# LCDmain.net
KiCad netlist of a schematic drawn in EAGLE
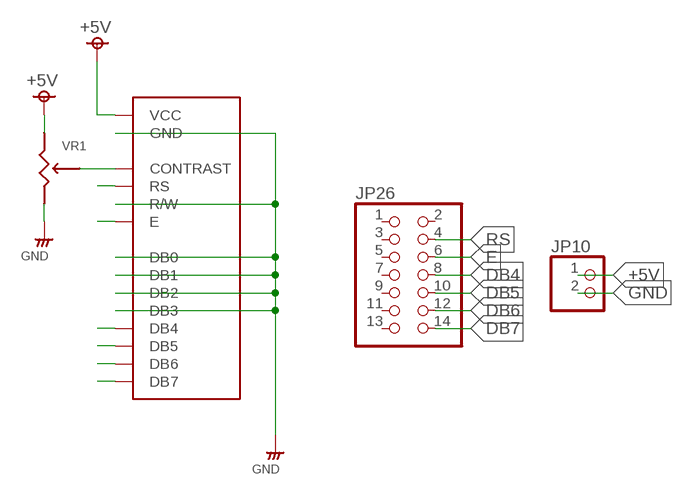
[diagram p0: schematic, sheet 1]

(export (version "E")
  (design (tool "Eeschema 10.0.6"))
  (components
    (comp (ref "JP10")
      (value "PINHD-1X2\"")
      (footprint "eagle-import:1_02")
      (libsource (lib "eagle-import") (part "PINHD-1X2{dblquote}"))
    )
    (comp (ref "JP26")
      (value "PINHD-2X7")
      (footprint "eagle-import:2X07")
      (libsource (lib "eagle-import") (part "PINHD-2X7"))
    )
    (comp (ref "U$1")
      (value "LCD_16X2")
      (footprint "eagle-import:LCD_16X2")
      (libsource (lib "eagle-import") (part "LCD_16X2"))
    )
    (comp (ref "VR1")
      (value "R-TRIM-3-L")
      (footprint "eagle-import:R_TRIM3")
      (libsource (lib "eagle-import") (part "R-TRIM-3-L"))
    )
  )
  (nets
    (net (code "1") (name "+5V") (class "Default")
      (node (ref "JP10") (pin "1") (pinfunction "1_1") (pintype "passive"))
      (node (ref "U$1") (pin "P$1") (pinfunction "VCC_P$1") (pintype "bidirectional"))
      (node (ref "VR1") (pin "1") (pinfunction "1_1") (pintype "bidirectional"))
    )
    (net (code "2") (name "DB4") (class "Default")
      (node (ref "JP26") (pin "8") (pinfunction "8_8") (pintype "passive"))
      (node (ref "U$1") (pin "P$11") (pinfunction "DB4_P$11") (pintype "bidirectional"))
    )
    (net (code "3") (name "DB5") (class "Default")
      (node (ref "JP26") (pin "10") (pinfunction "10_10") (pintype "passive"))
      (node (ref "U$1") (pin "P$12") (pinfunction "DB5_P$12") (pintype "bidirectional"))
    )
    (net (code "4") (name "DB6") (class "Default")
      (node (ref "JP26") (pin "12") (pinfunction "12_12") (pintype "passive"))
      (node (ref "U$1") (pin "P$13") (pinfunction "DB6_P$13") (pintype "bidirectional"))
    )
    (net (code "5") (name "DB7") (class "Default")
      (node (ref "JP26") (pin "14") (pinfunction "14_14") (pintype "passive"))
      (node (ref "U$1") (pin "P$14") (pinfunction "DB7_P$14") (pintype "bidirectional"))
    )
    (net (code "6") (name "E") (class "Default")
      (node (ref "JP26") (pin "6") (pinfunction "6_6") (pintype "passive"))
      (node (ref "U$1") (pin "P$6") (pinfunction "E_P$6") (pintype "bidirectional"))
    )
    (net (code "7") (name "GND") (class "Default")
      (node (ref "JP10") (pin "2") (pinfunction "2_2") (pintype "passive"))
      (node (ref "U$1") (pin "P$10") (pinfunction "DB3_P$10") (pintype "bidirectional"))
      (node (ref "U$1") (pin "P$2") (pinfunction "GND_P$2") (pintype "bidirectional"))
      (node (ref "U$1") (pin "P$5") (pinfunction "R/W_P$5") (pintype "bidirectional"))
      (node (ref "U$1") (pin "P$7") (pinfunction "DB0_P$7") (pintype "bidirectional"))
      (node (ref "U$1") (pin "P$8") (pinfunction "DB1_P$8") (pintype "bidirectional"))
      (node (ref "U$1") (pin "P$9") (pinfunction "DB2_P$9") (pintype "bidirectional"))
      (node (ref "VR1") (pin "3") (pinfunction "3_3") (pintype "bidirectional"))
    )
    (net (code "8") (name "Net-(U$1-CONTRAST)") (class "Default")
      (node (ref "U$1") (pin "P$3") (pinfunction "CONTRAST_P$3") (pintype "bidirectional"))
      (node (ref "VR1") (pin "2") (pinfunction "2_2") (pintype "bidirectional"))
    )
    (net (code "9") (name "RS") (class "Default")
      (node (ref "JP26") (pin "4") (pinfunction "4_4") (pintype "passive"))
      (node (ref "U$1") (pin "P$4") (pinfunction "RS_P$4") (pintype "bidirectional"))
    )
    (net (code "10") (name "unconnected-(JP26-Pad1)") (class "Default")
      (node (ref "JP26") (pin "1") (pinfunction "1_1") (pintype "passive"))
    )
    (net (code "11") (name "unconnected-(JP26-Pad2)") (class "Default")
      (node (ref "JP26") (pin "2") (pinfunction "2_2") (pintype "passive"))
    )
    (net (code "12") (name "unconnected-(JP26-Pad3)") (class "Default")
      (node (ref "JP26") (pin "3") (pinfunction "3_3") (pintype "passive"))
    )
    (net (code "13") (name "unconnected-(JP26-Pad5)") (class "Default")
      (node (ref "JP26") (pin "5") (pinfunction "5_5") (pintype "passive"))
    )
    (net (code "14") (name "unconnected-(JP26-Pad7)") (class "Default")
      (node (ref "JP26") (pin "7") (pinfunction "7_7") (pintype "passive"))
    )
    (net (code "15") (name "unconnected-(JP26-Pad9)") (class "Default")
      (node (ref "JP26") (pin "9") (pinfunction "9_9") (pintype "passive"))
    )
    (net (code "16") (name "unconnected-(JP26-Pad11)") (class "Default")
      (node (ref "JP26") (pin "11") (pinfunction "11_11") (pintype "passive"))
    )
    (net (code "17") (name "unconnected-(JP26-Pad13)") (class "Default")
      (node (ref "JP26") (pin "13") (pinfunction "13_13") (pintype "passive"))
    )
  )
)
